# PWR_Schem_1.net
KiCad netlist of a schematic drawn in Altium Designer
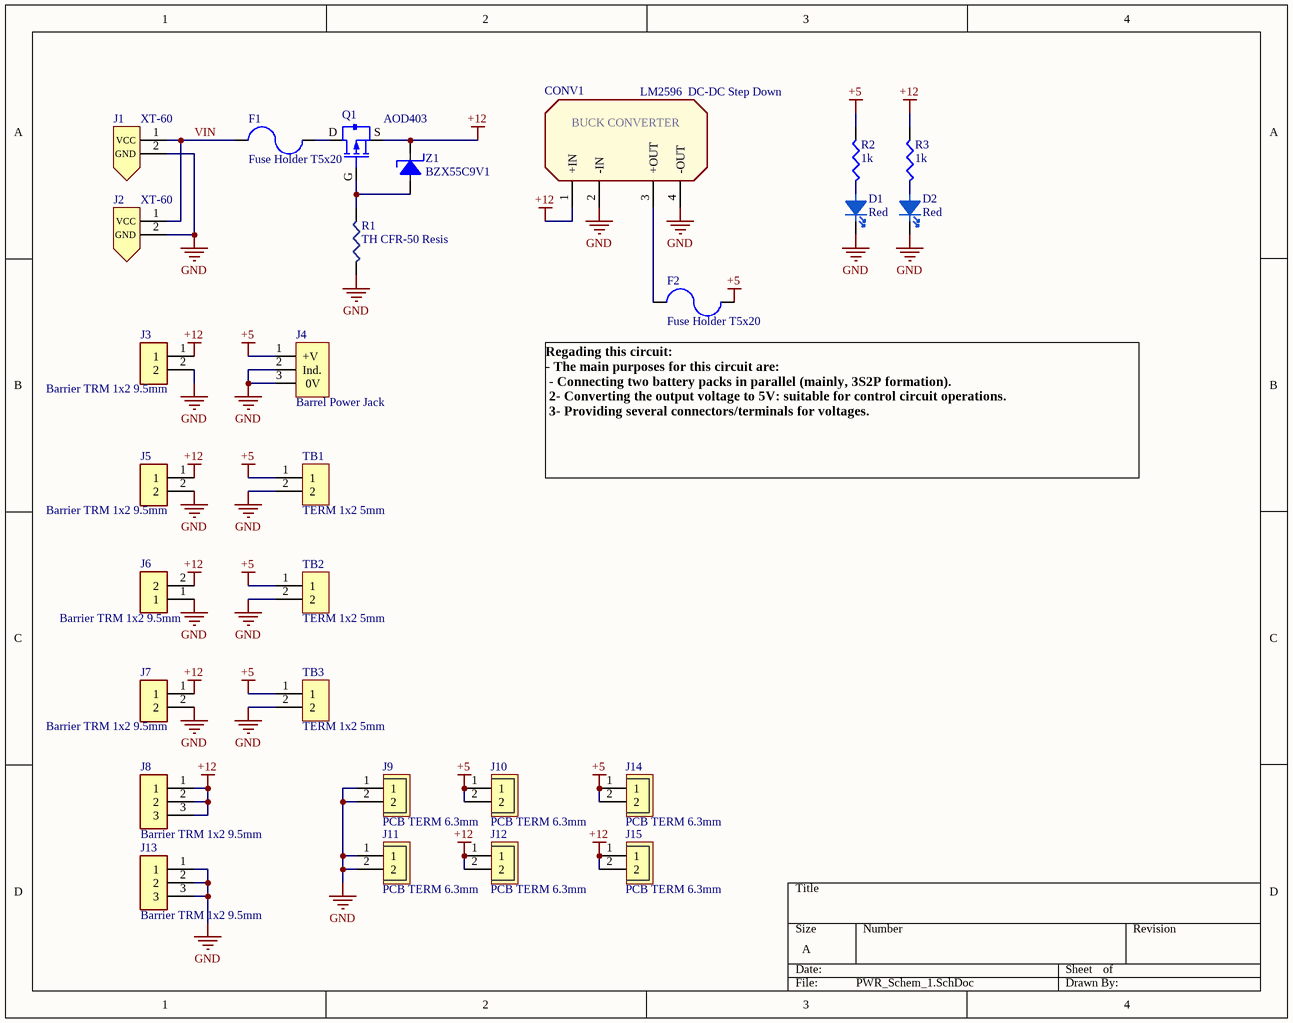
[diagram p0: PWR_Schem_1.SchDoc]

(export (version "E")
  (design (tool "Eeschema 10.0.6"))
  (components
    (comp (ref "CONV1")
      (value "LM2596  DC-DC Step Down")
      (footprint "DC_STP_DWN")
      (description "Conv DC-DC 4.5V to 40V Inv/Step Down Single-Out 1.2V to 37V 3A 6-Pin(5+Tab) TO-263 Tube")
      (libsource (lib "Schlib1") (part "Buck Conv."))
    )
    (comp (ref "D1")
      (value "Red")
      (footprint "LED_TH_2.54mm")
      (description "LED RED DIFF 5MM OVAL T/H")
      (libsource (lib "Schlib1") (part "TH Red LED 5mm"))
    )
    (comp (ref "D2")
      (value "Red")
      (footprint "LED_TH_2.54mm")
      (description "LED RED DIFF 5MM OVAL T/H")
      (libsource (lib "Schlib1") (part "TH Red LED 5mm"))
    )
    (comp (ref "F1")
      (value "Fuse Holder T5x20")
      (footprint "FUSE")
      (libsource (lib "Schlib1") (part "FUSE_T5x20"))
    )
    (comp (ref "F2")
      (value "Fuse Holder T5x20")
      (footprint "FUSE")
      (libsource (lib "Schlib1") (part "FUSE_T5x20"))
    )
    (comp (ref "J1")
      (value "XT-60")
      (footprint "XT-60_FEM")
      (description "XT60 CONNECTORS MALE/FEMALE PAIR")
      (libsource (lib "Schlib1") (part "XT-60 Power Female Con."))
    )
    (comp (ref "J2")
      (value "XT-60")
      (footprint "XT-60_FEM")
      (description "XT60 CONNECTORS MALE/FEMALE PAIR")
      (libsource (lib "Schlib1") (part "XT-60 Power Female Con."))
    )
    (comp (ref "J3")
      (value "Barrier TRM 1x2 9.5mm")
      (footprint "BARRIER_9.5MM")
      (description "CONN BARRIER STRIP 2CIRC 0.374\"")
      (libsource (lib "Schlib1") (part "Barrier BLK"))
    )
    (comp (ref "J4")
      (value "Barrel Power Jack")
      (footprint "pwr_Jack")
      (description "DC-Power Socket 12V 5A 2, 1mm Solder Eyel")
      (libsource (lib "Schlib1") (part "Con-Jack"))
    )
    (comp (ref "J5")
      (value "Barrier TRM 1x2 9.5mm")
      (footprint "BARRIER_9.5MM")
      (description "CONN BARRIER STRIP 2CIRC 0.374\"")
      (libsource (lib "Schlib1") (part "Barrier BLK"))
    )
    (comp (ref "J6")
      (value "Barrier TRM 1x2 9.5mm")
      (footprint "BARRIER_9.5MM")
      (description "CONN BARRIER STRIP 2CIRC 0.374\"")
      (libsource (lib "") (part "Barrier BLK_1"))
    )
    (comp (ref "J7")
      (value "Barrier TRM 1x2 9.5mm")
      (footprint "BARRIER_9.5MM")
      (description "CONN BARRIER STRIP 2CIRC 0.374\"")
      (libsource (lib "Schlib1") (part "Barrier BLK"))
    )
    (comp (ref "J8")
      (value "Barrier TRM 1x2 9.5mm")
      (footprint "BARRIER_3_9.5MM")
      (description "CONN BARRIER STRIP 3CIRC 0.374\"")
      (libsource (lib "Schlib1") (part "Barrier BLK_3"))
    )
    (comp (ref "J9")
      (value "PCB TERM 6.3mm")
      (footprint "PCB_TERM 6.3mm")
      (libsource (lib "Schlib1") (part "PCB Terminal"))
    )
    (comp (ref "J10")
      (value "PCB TERM 6.3mm")
      (footprint "PCB_TERM 6.3mm")
      (libsource (lib "Schlib1") (part "PCB Terminal"))
    )
    (comp (ref "J11")
      (value "PCB TERM 6.3mm")
      (footprint "PCB_TERM 6.3mm")
      (libsource (lib "Schlib1") (part "PCB Terminal"))
    )
    (comp (ref "J12")
      (value "PCB TERM 6.3mm")
      (footprint "PCB_TERM 6.3mm")
      (libsource (lib "Schlib1") (part "PCB Terminal"))
    )
    (comp (ref "J13")
      (value "Barrier TRM 1x2 9.5mm")
      (footprint "BARRIER_3_9.5MM")
      (description "CONN BARRIER STRIP 3CIRC 0.374\"")
      (libsource (lib "Schlib1") (part "Barrier BLK_3"))
    )
    (comp (ref "J14")
      (value "PCB TERM 6.3mm")
      (footprint "PCB_TERM 6.3mm")
      (libsource (lib "Schlib1") (part "PCB Terminal"))
    )
    (comp (ref "J15")
      (value "PCB TERM 6.3mm")
      (footprint "PCB_TERM 6.3mm")
      (libsource (lib "Schlib1") (part "PCB Terminal"))
    )
    (comp (ref "Q1")
      (value "AOD403")
      (footprint "DPAK")
      (description "MOSFET Transistor P-Channel 30V 15A 3.5V @ 250uA 6mΩ @ 20A,20V 2.5W TO-252-2(DPAK)")
      (libsource (lib "Schlib1") (part "AOD403"))
    )
    (comp (ref "R1")
      (value "TH CFR-50 Resis")
      (footprint "R_THT_CFR-50")
      (description "General Type Carbon Film Resistor 330Ohm 1/2W 5% Axial Bulk")
      (fields (field (name "TOLERANCE") "5%"))
      (libsource (lib "Schlib1") (part "TH CFR-50 Resis"))
    )
    (comp (ref "R2")
      (value "1k")
      (footprint "R_THT_CFR-25")
      (description "CFR Series 0.25 W 1 KOhm ±5 % -350 to 500 ppm/°C Carbon Film Resistor")
      (fields (field (name "TOLERANCE") "5%"))
      (libsource (lib "Schlib1") (part "TH CFR-25 Resis"))
    )
    (comp (ref "R3")
      (value "1k")
      (footprint "R_THT_CFR-25")
      (description "CFR Series 0.25 W 1 KOhm ±5 % -350 to 500 ppm/°C Carbon Film Resistor")
      (fields (field (name "TOLERANCE") "5%"))
      (libsource (lib "Schlib1") (part "TH CFR-25 Resis"))
    )
    (comp (ref "TB1")
      (value "TERM 1x2 5mm")
      (footprint "Terminal_5mm")
      (fields (field (name "VOLTAGE") "300V"))
      (libsource (lib "Schlib1") (part "Terminal BLK Green"))
    )
    (comp (ref "TB2")
      (value "TERM 1x2 5mm")
      (footprint "Terminal_5mm")
      (fields (field (name "VOLTAGE") "300V"))
      (libsource (lib "Schlib1") (part "Terminal BLK Green"))
    )
    (comp (ref "TB3")
      (value "TERM 1x2 5mm")
      (footprint "Terminal_5mm")
      (fields (field (name "VOLTAGE") "300V"))
      (libsource (lib "Schlib1") (part "Terminal BLK Green"))
    )
    (comp (ref "Z1")
      (value "BZX55C9V1")
      (footprint "DO-35")
      (description "TH Zener Diode DO-35")
      (libsource (lib "Schlib1") (part "Zener_DO-35"))
    )
  )
  (nets
    (net (code "1") (name "+5") (class "Default")
      (node (ref "F2") (pin "2") (pinfunction "2_2") (pintype "passive"))
      (node (ref "J10") (pin "1") (pinfunction "1_1") (pintype "passive"))
      (node (ref "J10") (pin "2") (pinfunction "2_2") (pintype "passive"))
      (node (ref "J14") (pin "1") (pinfunction "1_1") (pintype "passive"))
      (node (ref "J14") (pin "2") (pinfunction "2_2") (pintype "passive"))
      (node (ref "J4") (pin "1") (pinfunction "+V_1") (pintype "passive"))
      (node (ref "R2") (pin "2") (pinfunction "2_2") (pintype "passive"))
      (node (ref "TB1") (pin "1") (pinfunction "1_1") (pintype "passive"))
      (node (ref "TB2") (pin "1") (pinfunction "1_1") (pintype "passive"))
      (node (ref "TB3") (pin "1") (pinfunction "1_1") (pintype "passive"))
    )
    (net (code "2") (name "+12") (class "Default")
      (node (ref "CONV1") (pin "1") (pinfunction "+IN_1") (pintype "passive"))
      (node (ref "J12") (pin "1") (pinfunction "1_1") (pintype "passive"))
      (node (ref "J12") (pin "2") (pinfunction "2_2") (pintype "passive"))
      (node (ref "J15") (pin "1") (pinfunction "1_1") (pintype "passive"))
      (node (ref "J15") (pin "2") (pinfunction "2_2") (pintype "passive"))
      (node (ref "J3") (pin "1") (pinfunction "1_1") (pintype "passive"))
      (node (ref "J5") (pin "1") (pinfunction "1_1") (pintype "passive"))
      (node (ref "J6") (pin "2") (pinfunction "2_2") (pintype "passive"))
      (node (ref "J7") (pin "1") (pinfunction "1_1") (pintype "passive"))
      (node (ref "J8") (pin "1") (pinfunction "1_1") (pintype "passive"))
      (node (ref "J8") (pin "2") (pinfunction "2_2") (pintype "passive"))
      (node (ref "J8") (pin "3") (pinfunction "3_3") (pintype "passive"))
      (node (ref "Q1") (pin "S") (pinfunction "S_S") (pintype "passive"))
      (node (ref "R3") (pin "2") (pinfunction "2_2") (pintype "passive"))
      (node (ref "Z1") (pin "K") (pinfunction "Cathode_K") (pintype "passive"))
    )
    (net (code "3") (name "/VIN") (class "Default")
      (node (ref "F1") (pin "1") (pinfunction "1_1") (pintype "passive"))
      (node (ref "J1") (pin "1") (pinfunction "VCC_1") (pintype "passive"))
      (node (ref "J2") (pin "1") (pinfunction "VCC_1") (pintype "passive"))
    )
    (net (code "4") (name "GND") (class "Default")
      (node (ref "CONV1") (pin "2") (pinfunction "-IN_2") (pintype "passive"))
      (node (ref "CONV1") (pin "4") (pinfunction "-OUT_4") (pintype "passive"))
      (node (ref "D1") (pin "2") (pinfunction "Cathode_2") (pintype "passive"))
      (node (ref "D2") (pin "2") (pinfunction "Cathode_2") (pintype "passive"))
      (node (ref "J1") (pin "2") (pinfunction "GND_2") (pintype "passive"))
      (node (ref "J11") (pin "1") (pinfunction "1_1") (pintype "passive"))
      (node (ref "J11") (pin "2") (pinfunction "2_2") (pintype "passive"))
      (node (ref "J13") (pin "1") (pinfunction "1_1") (pintype "passive"))
      (node (ref "J13") (pin "2") (pinfunction "2_2") (pintype "passive"))
      (node (ref "J13") (pin "3") (pinfunction "3_3") (pintype "passive"))
      (node (ref "J2") (pin "2") (pinfunction "GND_2") (pintype "passive"))
      (node (ref "J3") (pin "2") (pinfunction "2_2") (pintype "passive"))
      (node (ref "J4") (pin "2") (pinfunction "Ind._2") (pintype "passive"))
      (node (ref "J4") (pin "3") (pinfunction "_0V_3") (pintype "passive"))
      (node (ref "J5") (pin "2") (pinfunction "2_2") (pintype "passive"))
      (node (ref "J6") (pin "1") (pinfunction "1_1") (pintype "passive"))
      (node (ref "J7") (pin "2") (pinfunction "2_2") (pintype "passive"))
      (node (ref "J9") (pin "1") (pinfunction "1_1") (pintype "passive"))
      (node (ref "J9") (pin "2") (pinfunction "2_2") (pintype "passive"))
      (node (ref "R1") (pin "1") (pinfunction "1_1") (pintype "passive"))
      (node (ref "TB1") (pin "2") (pinfunction "2_2") (pintype "passive"))
      (node (ref "TB2") (pin "2") (pinfunction "2_2") (pintype "passive"))
      (node (ref "TB3") (pin "2") (pinfunction "2_2") (pintype "passive"))
    )
    (net (code "5") (name "Net-(CONV1-+OUT)") (class "Default")
      (node (ref "CONV1") (pin "3") (pinfunction "+OUT_3") (pintype "passive"))
      (node (ref "F2") (pin "1") (pinfunction "1_1") (pintype "passive"))
    )
    (net (code "6") (name "Net-(D1-Anode)") (class "Default")
      (node (ref "D1") (pin "1") (pinfunction "Anode_1") (pintype "passive"))
      (node (ref "R2") (pin "1") (pinfunction "1_1") (pintype "passive"))
    )
    (net (code "7") (name "Net-(D2-Anode)") (class "Default")
      (node (ref "D2") (pin "1") (pinfunction "Anode_1") (pintype "passive"))
      (node (ref "R3") (pin "1") (pinfunction "1_1") (pintype "passive"))
    )
    (net (code "8") (name "Net-(F1-Pad2)") (class "Default")
      (node (ref "F1") (pin "2") (pinfunction "2_2") (pintype "passive"))
      (node (ref "Q1") (pin "D") (pinfunction "D_D") (pintype "passive"))
    )
    (net (code "9") (name "Net-(Z1-Anode)") (class "Default")
      (node (ref "Q1") (pin "G") (pinfunction "G_G") (pintype "passive"))
      (node (ref "R1") (pin "2") (pinfunction "2_2") (pintype "passive"))
      (node (ref "Z1") (pin "A") (pinfunction "Anode_A") (pintype "passive"))
    )
  )
)
